# Adafruit_ADS1115_ADC_STEMMA_QT.net
KiCad netlist of a schematic drawn in EAGLE
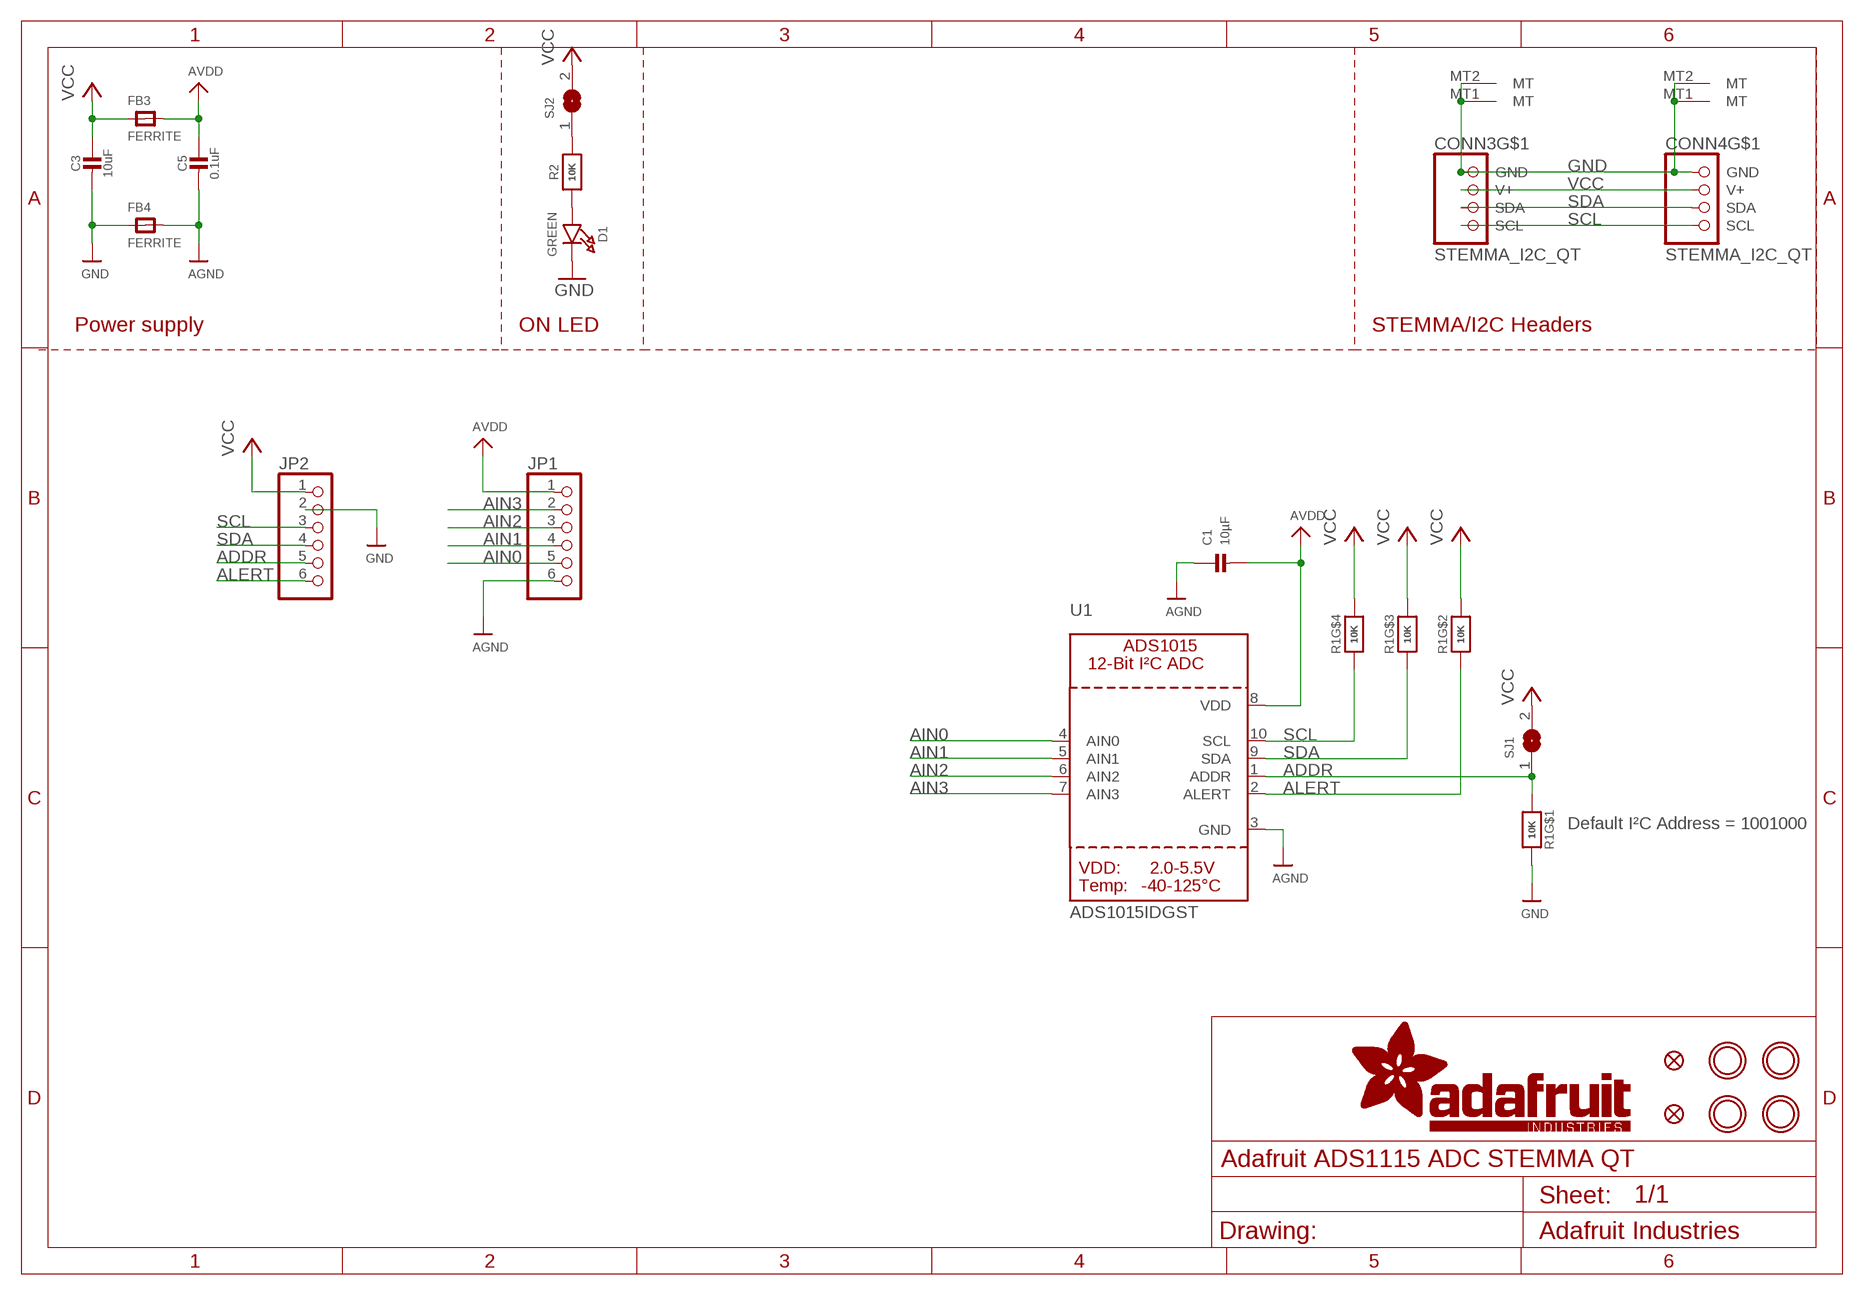
[diagram p0: schematic, sheet 1]

(export (version "E")
  (design (tool "Eeschema 10.0.6"))
  (components
    (comp (ref "C1")
      (value "10µF")
      (footprint "eagle-import:0805-NO")
      (libsource (lib "eagle-import") (part "CAP_CERAMIC0805-NOOUTLINE"))
    )
    (comp (ref "C3")
      (value "10uF")
      (footprint "eagle-import:0805-NO")
      (libsource (lib "eagle-import") (part "CAP_CERAMIC0805-NOOUTLINE"))
    )
    (comp (ref "C5")
      (value "0.1uF")
      (footprint "eagle-import:0603-NO")
      (libsource (lib "eagle-import") (part "CAP_CERAMIC0603_NO"))
    )
    (comp (ref "CONN3")
      (value "STEMMA_I2C_QT")
      (footprint "eagle-import:JST_SH4")
      (libsource (lib "eagle-import") (part "STEMMA_I2C_QT"))
    )
    (comp (ref "CONN4")
      (value "STEMMA_I2C_QT")
      (footprint "eagle-import:JST_SH4")
      (libsource (lib "eagle-import") (part "STEMMA_I2C_QT"))
    )
    (comp (ref "D1")
      (value "GREEN")
      (footprint "eagle-import:CHIPLED_0603_NOOUTLINE")
      (libsource (lib "eagle-import") (part "LED0603_NOOUTLINE"))
    )
    (comp (ref "FB3")
      (value "FERRITE")
      (footprint "eagle-import:0603-NO")
      (libsource (lib "eagle-import") (part "FERRITE-0603NO"))
    )
    (comp (ref "FB4")
      (value "FERRITE")
      (footprint "eagle-import:0603-NO")
      (libsource (lib "eagle-import") (part "FERRITE-0603NO"))
    )
    (comp (ref "FID3")
      (value "FIDUCIAL_1MM")
      (footprint "eagle-import:FIDUCIAL_1MM")
      (libsource (lib "eagle-import") (part "FIDUCIAL_1MM"))
    )
    (comp (ref "FID4")
      (value "FIDUCIAL_1MM")
      (footprint "eagle-import:FIDUCIAL_1MM")
      (libsource (lib "eagle-import") (part "FIDUCIAL_1MM"))
    )
    (comp (ref "JP1")
      (value "HEADER-1X670MIL")
      (footprint "eagle-import:1X06_ROUND_70")
      (libsource (lib "eagle-import") (part "HEADER-1X670MIL"))
    )
    (comp (ref "JP2")
      (value "HEADER-1X670MIL")
      (footprint "eagle-import:1X06_ROUND_70")
      (libsource (lib "eagle-import") (part "HEADER-1X670MIL"))
    )
    (comp (ref "R1")
      (value "10K")
      (footprint "eagle-import:RESPACK_4X0603")
      (libsource (lib "eagle-import") (part "RESISTOR_4PACK"))
    )
    (comp (ref "R2")
      (value "10K")
      (footprint "eagle-import:0603-NO")
      (libsource (lib "eagle-import") (part "RESISTOR_0603_NOOUT"))
    )
    (comp (ref "SJ1")
      (value "SOLDERJUMPER")
      (footprint "eagle-import:SOLDERJUMPER_ARROW_NOPASTE")
      (libsource (lib "eagle-import") (part "SOLDERJUMPER"))
    )
    (comp (ref "SJ2")
      (value "SOLDERJUMPERCLOSED")
      (footprint "eagle-import:SOLDERJUMPER_CLOSEDWIRE")
      (libsource (lib "eagle-import") (part "SOLDERJUMPERCLOSED"))
    )
    (comp (ref "U$25")
      (value "MOUNTINGHOLE2.5")
      (footprint "eagle-import:MOUNTINGHOLE_2.5_PLATED")
      (libsource (lib "eagle-import") (part "MOUNTINGHOLE2.5"))
    )
    (comp (ref "U$27")
      (value "MOUNTINGHOLE2.5")
      (footprint "eagle-import:MOUNTINGHOLE_2.5_PLATED")
      (libsource (lib "eagle-import") (part "MOUNTINGHOLE2.5"))
    )
    (comp (ref "U$29")
      (value "MOUNTINGHOLE2.5")
      (footprint "eagle-import:MOUNTINGHOLE_2.5_PLATED")
      (libsource (lib "eagle-import") (part "MOUNTINGHOLE2.5"))
    )
    (comp (ref "U$30")
      (value "MOUNTINGHOLE2.5")
      (footprint "eagle-import:MOUNTINGHOLE_2.5_PLATED")
      (libsource (lib "eagle-import") (part "MOUNTINGHOLE2.5"))
    )
    (comp (ref "U1")
      (value "ADS1015IDGST")
      (footprint "eagle-import:MSOP10")
      (libsource (lib "eagle-import") (part "ADC_ADS1015"))
    )
  )
  (nets
    (net (code "1") (name "/ADDR") (class "Default")
      (node (ref "JP2") (pin "5") (pinfunction "5_5") (pintype "passive"))
      (node (ref "R1") (pin "1") (pinfunction "1_1") (pintype "passive"))
      (node (ref "SJ1") (pin "1") (pinfunction "1_1") (pintype "passive"))
      (node (ref "U1") (pin "1") (pinfunction "ADDR_1") (pintype "bidirectional"))
    )
    (net (code "2") (name "/AIN0") (class "Default")
      (node (ref "JP1") (pin "5") (pinfunction "5_5") (pintype "passive"))
      (node (ref "U1") (pin "4") (pinfunction "AIN0_4") (pintype "bidirectional"))
    )
    (net (code "3") (name "/AIN1") (class "Default")
      (node (ref "JP1") (pin "4") (pinfunction "4_4") (pintype "passive"))
      (node (ref "U1") (pin "5") (pinfunction "AIN1_5") (pintype "bidirectional"))
    )
    (net (code "4") (name "/AIN2") (class "Default")
      (node (ref "JP1") (pin "3") (pinfunction "3_3") (pintype "passive"))
      (node (ref "U1") (pin "6") (pinfunction "AIN2_6") (pintype "bidirectional"))
    )
    (net (code "5") (name "/AIN3") (class "Default")
      (node (ref "JP1") (pin "2") (pinfunction "2_2") (pintype "passive"))
      (node (ref "U1") (pin "7") (pinfunction "AIN3_7") (pintype "bidirectional"))
    )
    (net (code "6") (name "/ALERT") (class "Default")
      (node (ref "JP2") (pin "6") (pinfunction "6_6") (pintype "passive"))
      (node (ref "R1") (pin "2") (pinfunction "1_2") (pintype "passive"))
      (node (ref "U1") (pin "2") (pinfunction "ALERT_2") (pintype "bidirectional"))
    )
    (net (code "7") (name "/SCL") (class "Default")
      (node (ref "CONN3") (pin "4") (pinfunction "SCL_4") (pintype "passive"))
      (node (ref "CONN4") (pin "4") (pinfunction "SCL_4") (pintype "passive"))
      (node (ref "JP2") (pin "3") (pinfunction "3_3") (pintype "passive"))
      (node (ref "R1") (pin "4") (pinfunction "1_4") (pintype "passive"))
      (node (ref "U1") (pin "10") (pinfunction "SCL_10") (pintype "bidirectional"))
    )
    (net (code "8") (name "/SDA") (class "Default")
      (node (ref "CONN3") (pin "3") (pinfunction "SDA_3") (pintype "passive"))
      (node (ref "CONN4") (pin "3") (pinfunction "SDA_3") (pintype "passive"))
      (node (ref "JP2") (pin "4") (pinfunction "4_4") (pintype "passive"))
      (node (ref "R1") (pin "3") (pinfunction "1_3") (pintype "passive"))
      (node (ref "U1") (pin "9") (pinfunction "SDA_9") (pintype "bidirectional"))
    )
    (net (code "9") (name "AGND") (class "Default")
      (node (ref "C1") (pin "1") (pinfunction "1_1") (pintype "passive"))
      (node (ref "C5") (pin "2") (pinfunction "2_2") (pintype "passive"))
      (node (ref "FB4") (pin "2") (pinfunction "P$2_2") (pintype "passive"))
      (node (ref "JP1") (pin "6") (pinfunction "6_6") (pintype "passive"))
      (node (ref "U1") (pin "3") (pinfunction "GND_3") (pintype "bidirectional"))
    )
    (net (code "10") (name "AVDD") (class "Default")
      (node (ref "C1") (pin "2") (pinfunction "2_2") (pintype "passive"))
      (node (ref "C5") (pin "1") (pinfunction "1_1") (pintype "passive"))
      (node (ref "FB3") (pin "2") (pinfunction "P$2_2") (pintype "passive"))
      (node (ref "JP1") (pin "1") (pinfunction "1_1") (pintype "passive"))
      (node (ref "U1") (pin "8") (pinfunction "VDD_8") (pintype "bidirectional"))
    )
    (net (code "11") (name "GND") (class "Default")
      (node (ref "C3") (pin "2") (pinfunction "2_2") (pintype "passive"))
      (node (ref "CONN3") (pin "1") (pinfunction "GND_1") (pintype "passive"))
      (node (ref "CONN3") (pin "MT1") (pinfunction "MT_MT1") (pintype "bidirectional"))
      (node (ref "CONN3") (pin "MT2") (pinfunction "MT_MT2") (pintype "bidirectional"))
      (node (ref "CONN4") (pin "1") (pinfunction "GND_1") (pintype "passive"))
      (node (ref "CONN4") (pin "MT1") (pinfunction "MT_MT1") (pintype "bidirectional"))
      (node (ref "CONN4") (pin "MT2") (pinfunction "MT_MT2") (pintype "bidirectional"))
      (node (ref "D1") (pin "C") (pinfunction "C_C") (pintype "passive"))
      (node (ref "FB4") (pin "1") (pinfunction "P$1_1") (pintype "passive"))
      (node (ref "JP2") (pin "2") (pinfunction "2_2") (pintype "passive"))
      (node (ref "R1") (pin "8") (pinfunction "2_8") (pintype "passive"))
    )
    (net (code "12") (name "Net-(D1-PadA)") (class "Default")
      (node (ref "D1") (pin "A") (pinfunction "A_A") (pintype "passive"))
      (node (ref "R2") (pin "1") (pinfunction "1_1") (pintype "passive"))
    )
    (net (code "13") (name "Net-(R2-Pad2)") (class "Default")
      (node (ref "R2") (pin "2") (pinfunction "2_2") (pintype "passive"))
      (node (ref "SJ2") (pin "1") (pinfunction "1_1") (pintype "passive"))
    )
    (net (code "14") (name "VCC") (class "Default")
      (node (ref "C3") (pin "1") (pinfunction "1_1") (pintype "passive"))
      (node (ref "CONN3") (pin "2") (pinfunction "V+_2") (pintype "passive"))
      (node (ref "CONN4") (pin "2") (pinfunction "V+_2") (pintype "passive"))
      (node (ref "FB3") (pin "1") (pinfunction "P$1_1") (pintype "passive"))
      (node (ref "JP2") (pin "1") (pinfunction "1_1") (pintype "passive"))
      (node (ref "R1") (pin "5") (pinfunction "2_5") (pintype "passive"))
      (node (ref "R1") (pin "6") (pinfunction "2_6") (pintype "passive"))
      (node (ref "R1") (pin "7") (pinfunction "2_7") (pintype "passive"))
      (node (ref "SJ1") (pin "2") (pinfunction "2_2") (pintype "passive"))
      (node (ref "SJ2") (pin "2") (pinfunction "2_2") (pintype "passive"))
    )
  )
)
